# Teknic_motor_io.net
KiCad netlist of a schematic drawn in EAGLE
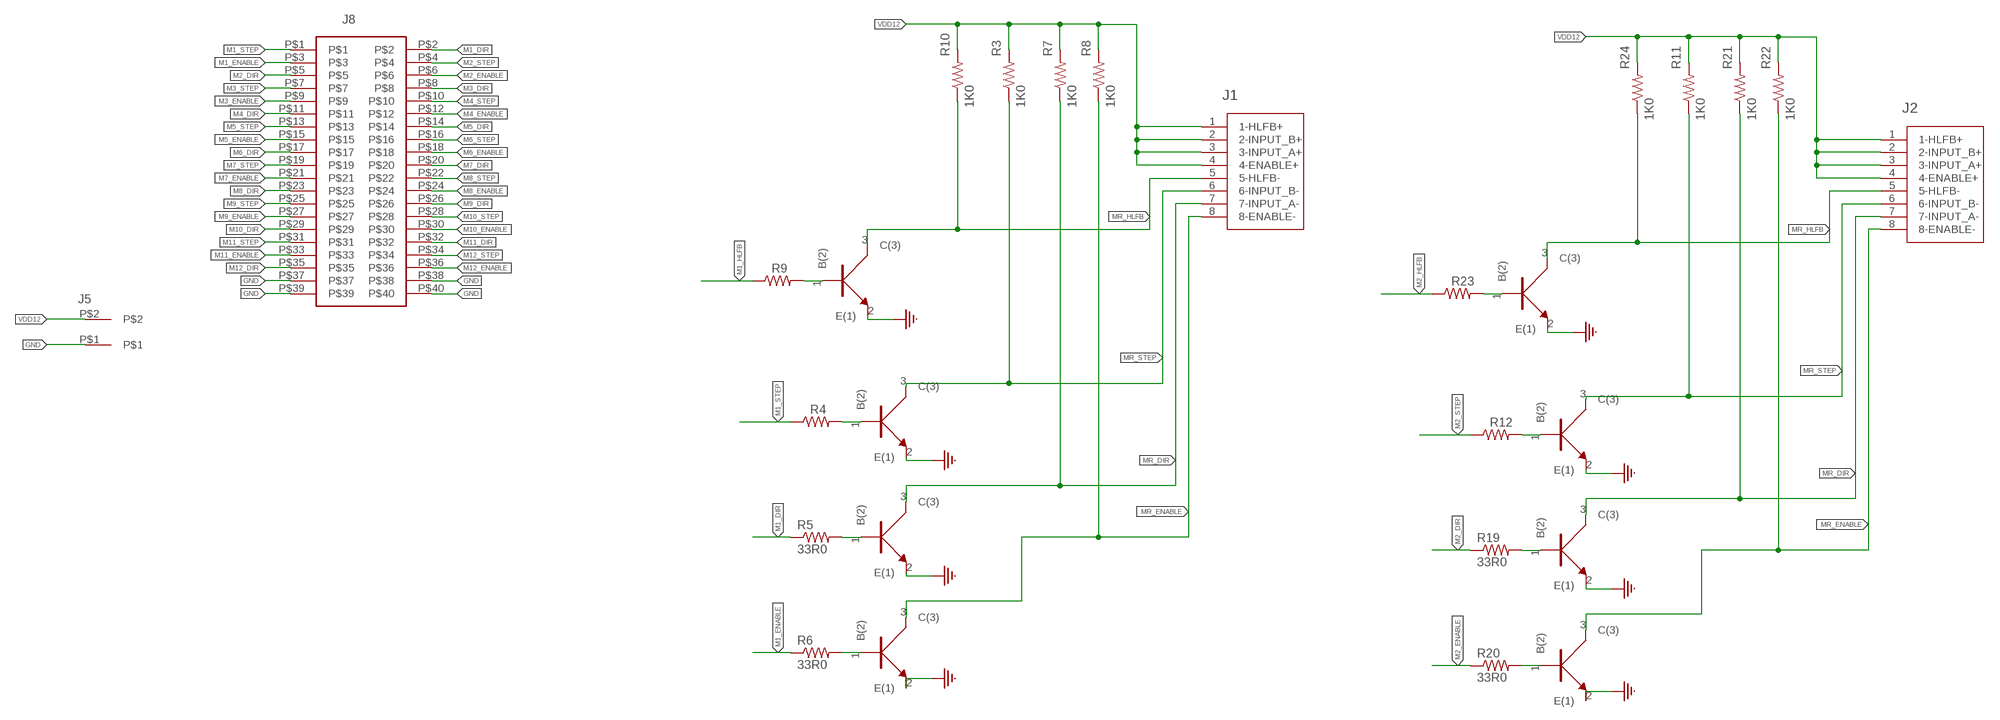
[diagram p0: schematic, sheet 1, part 1 of 3]
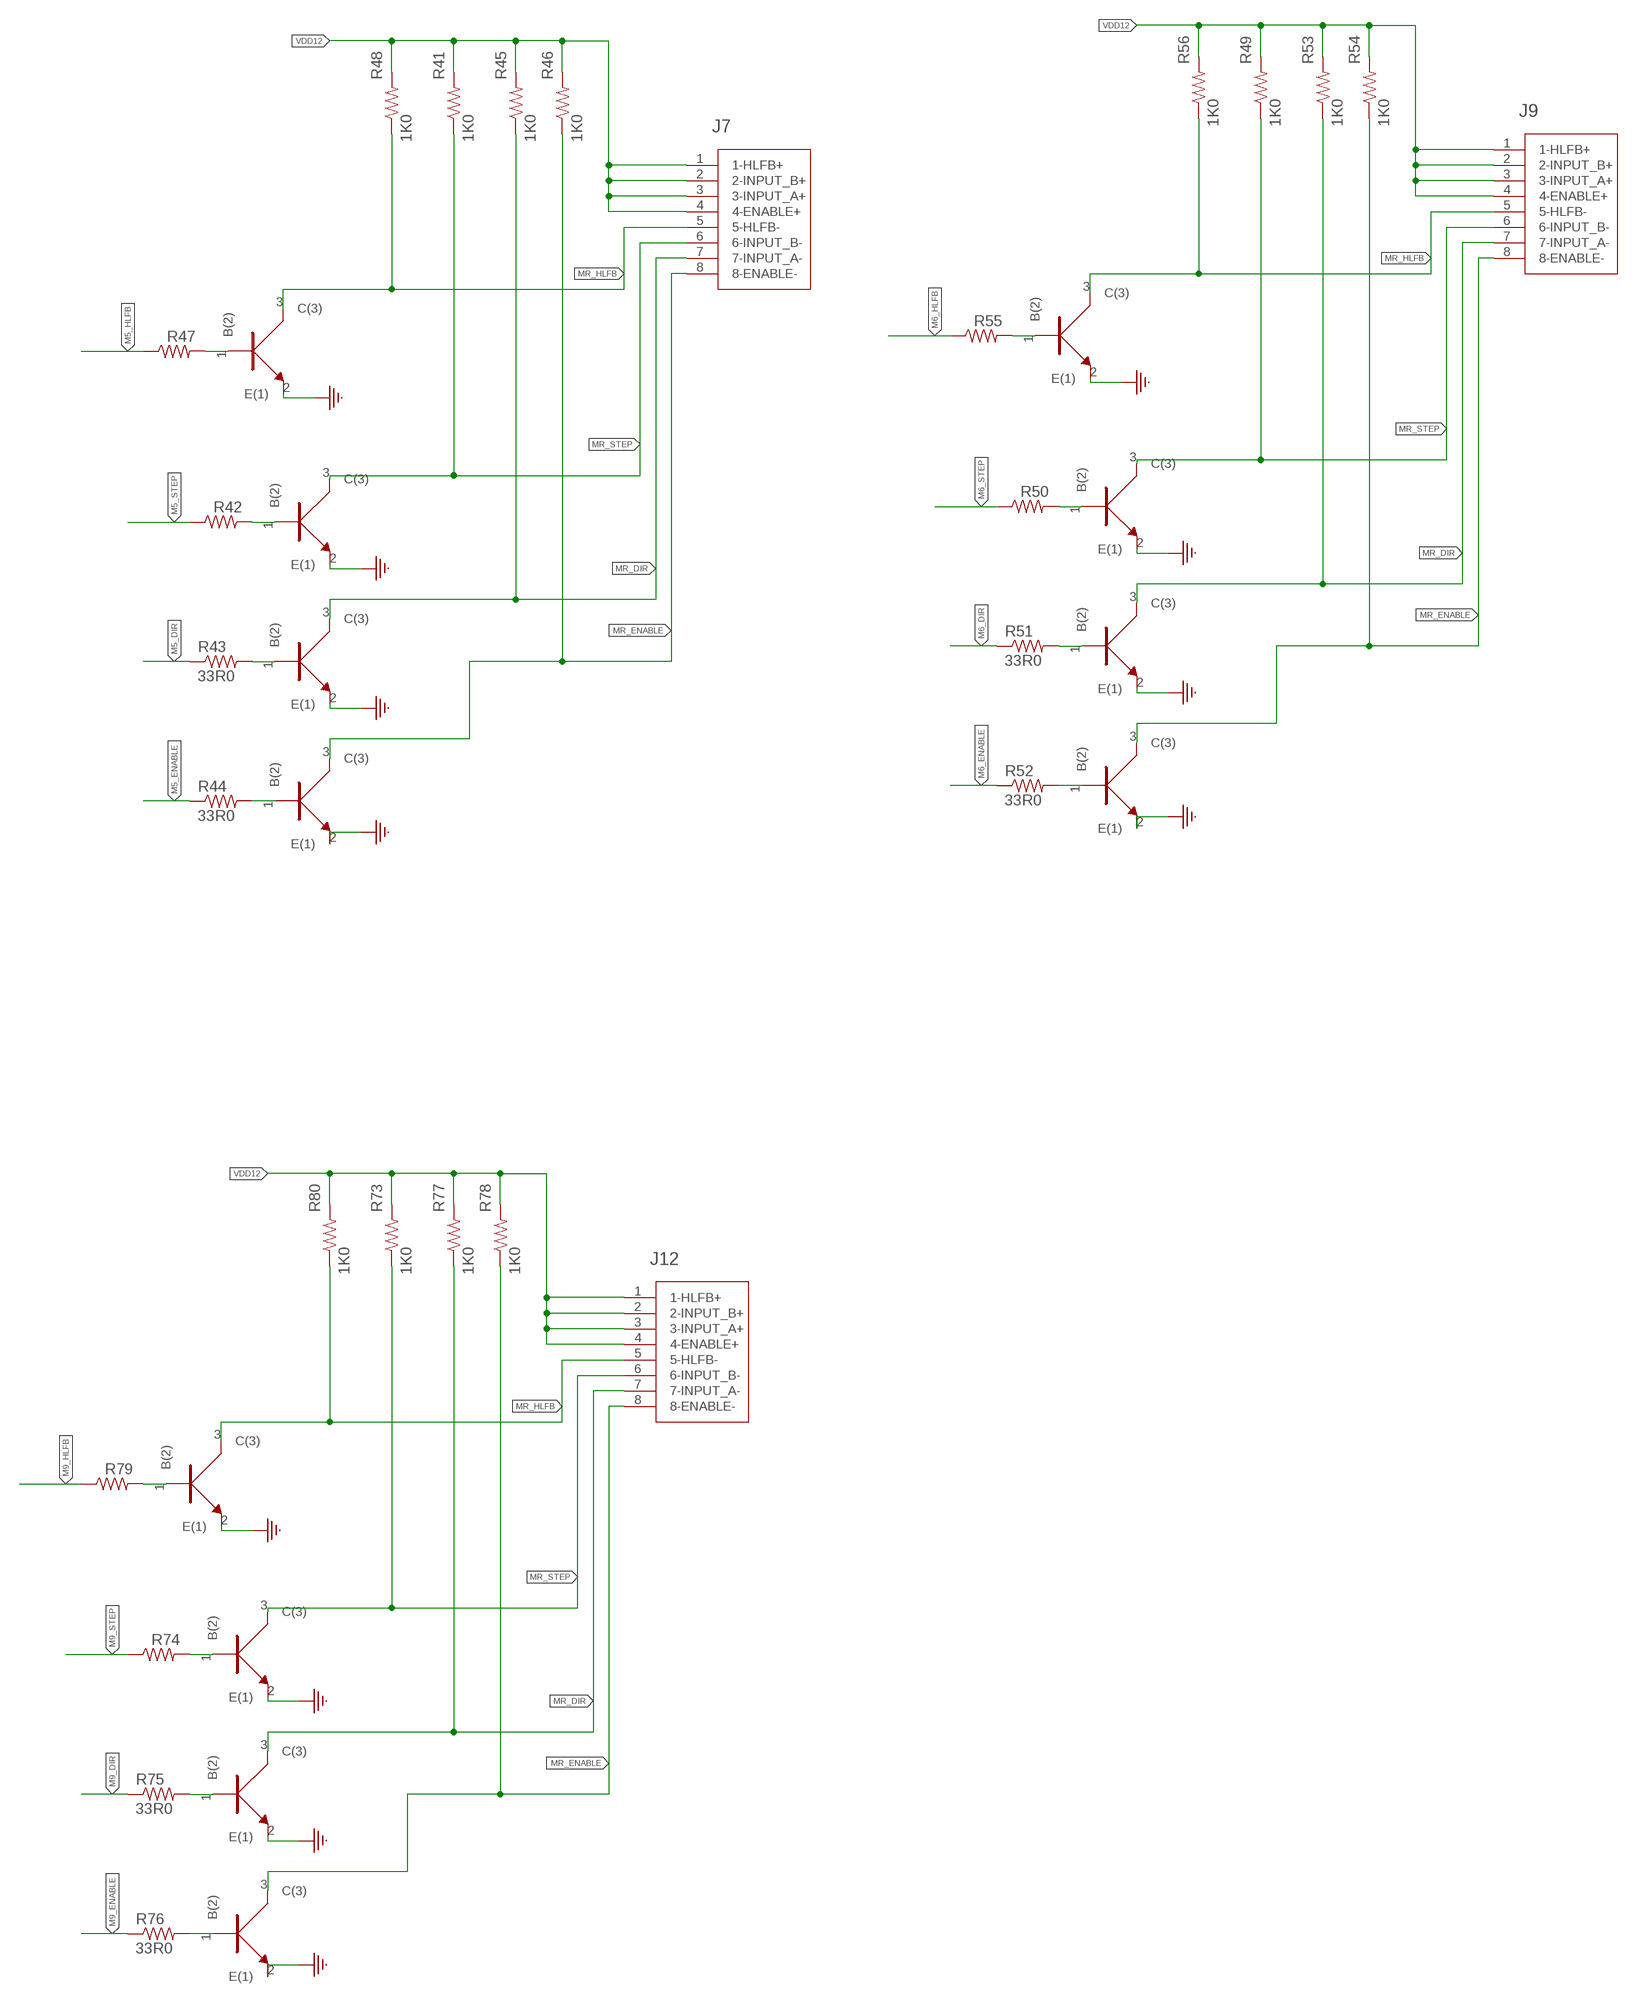
[diagram p1: schematic, sheet 1, part 2 of 3]
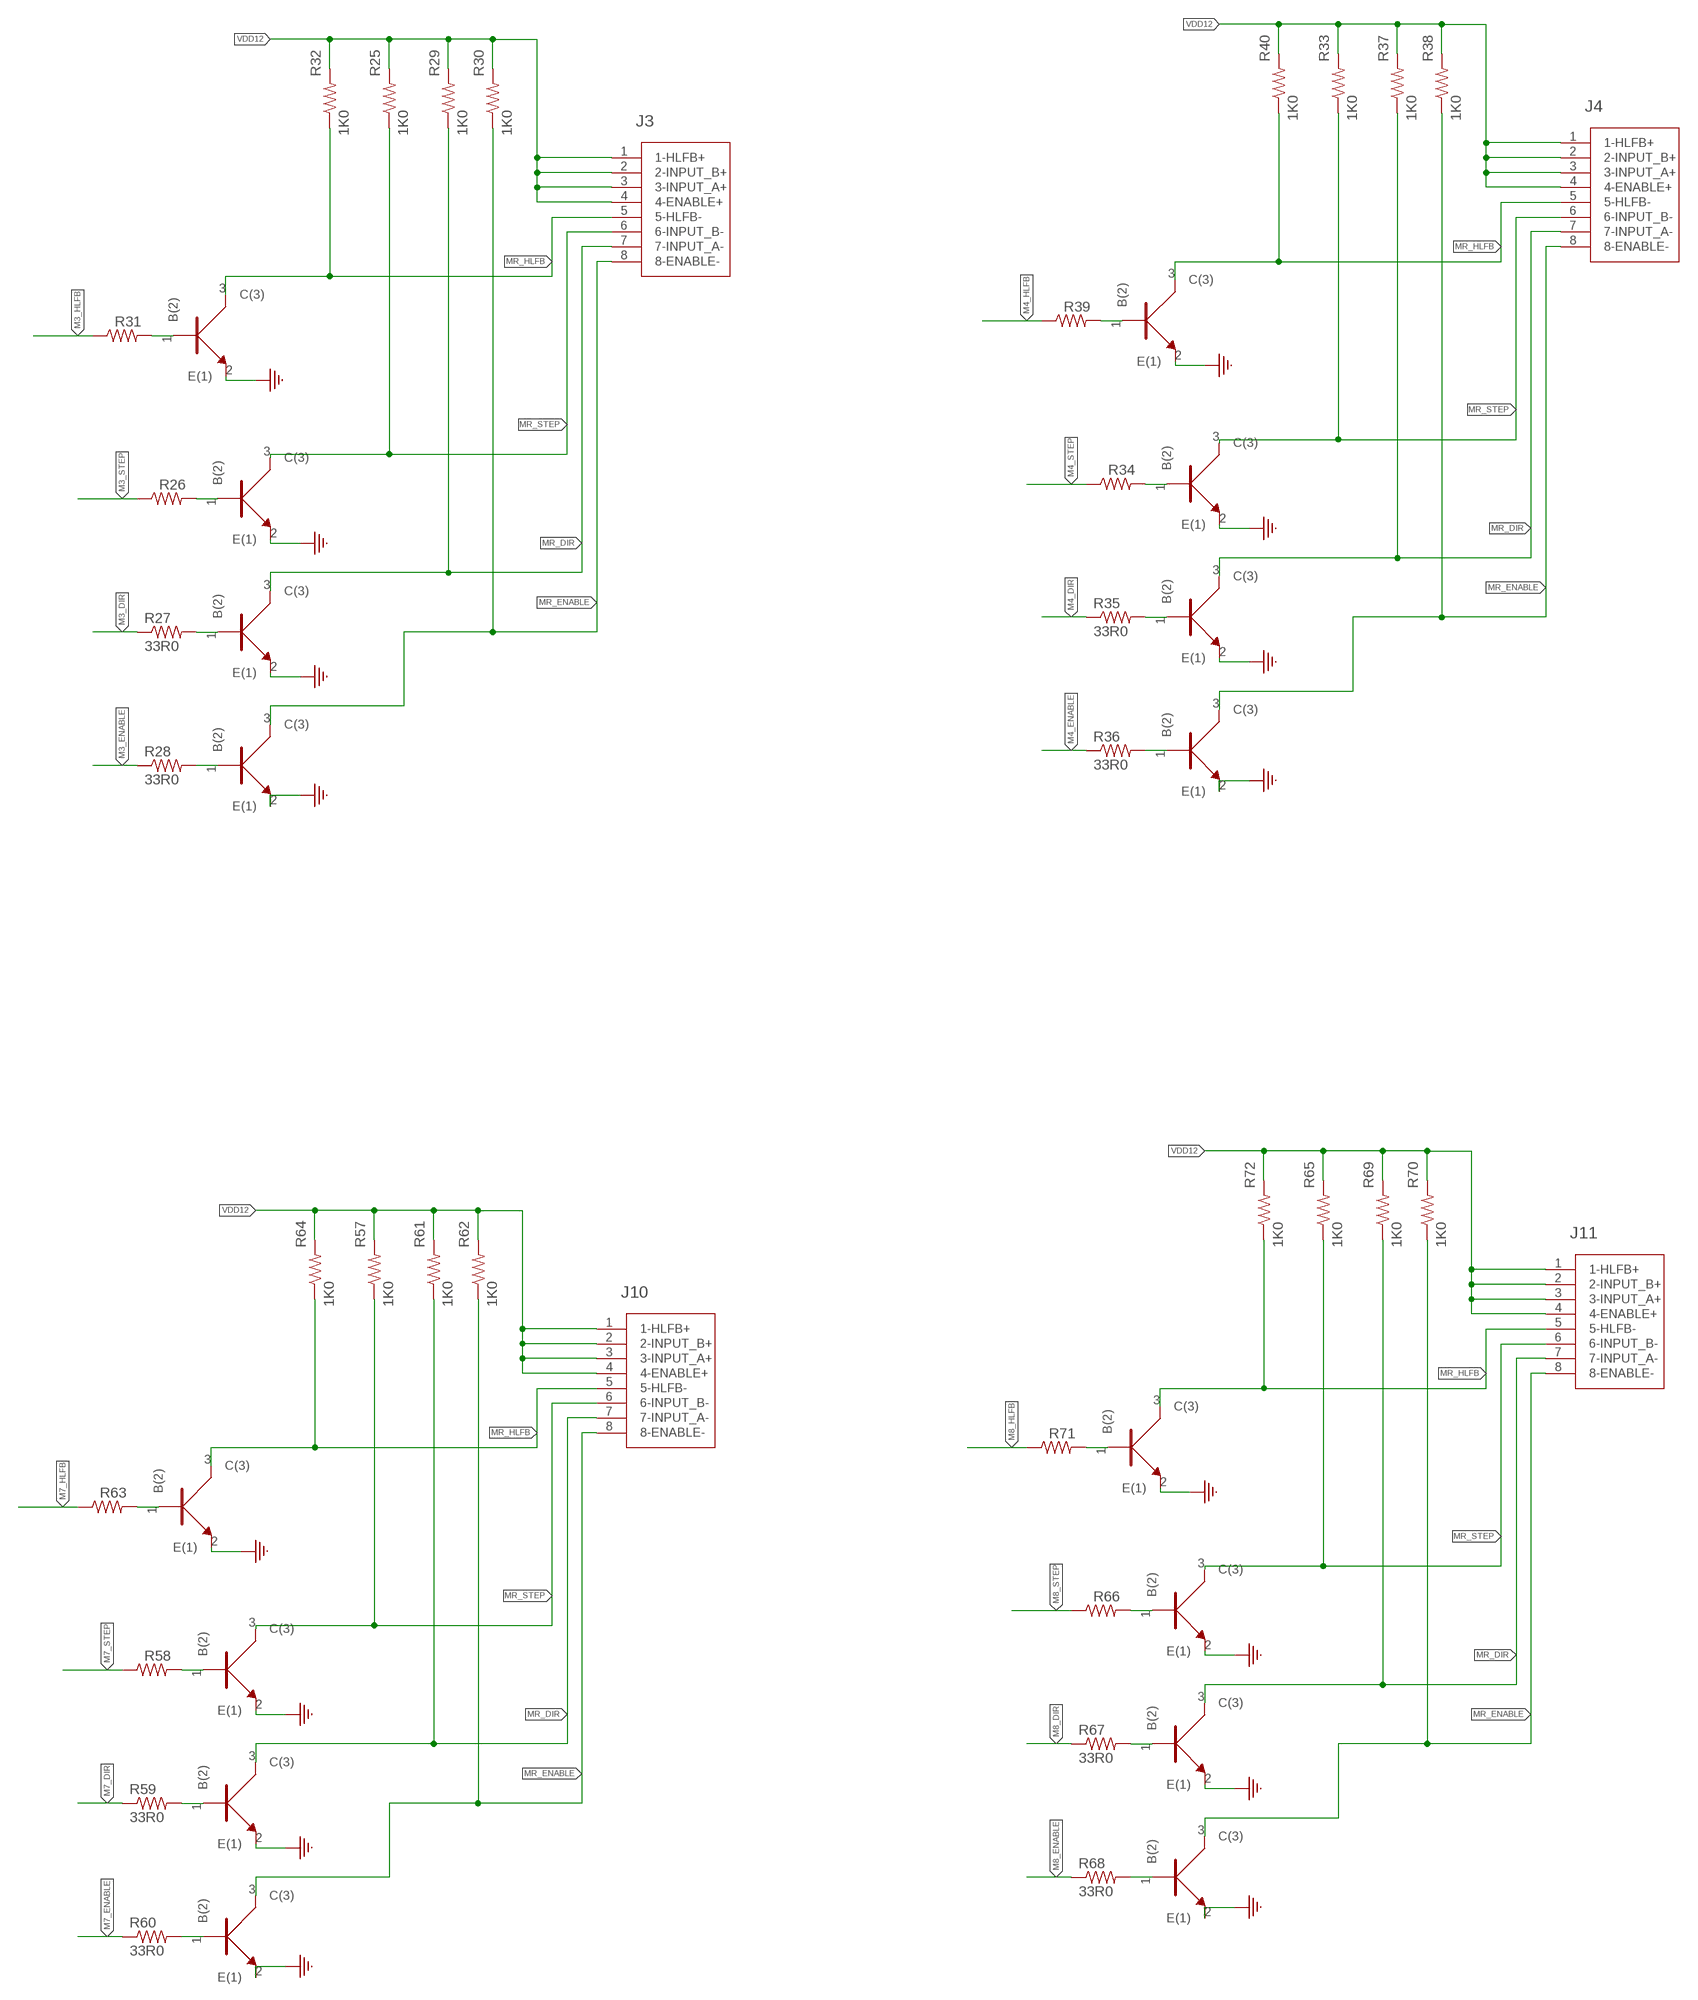
[diagram p2: schematic, sheet 1, part 3 of 3]

(export (version "E")
  (design (tool "Eeschema 10.0.6"))
  (components
    (comp (ref "J1")
      (value "TEKNIC_8PIN_MOTOR")
      (footprint "eagle-import:CON_39281083")
      (fields
        (field (name "MANUFACTURER_PART_NUMBER") "39281083")
        (field (name "COPYRIGHT") "Copyright (C) 2022 Ultra Librarian. All rights reserved.")
      )
      (libsource (lib "eagle-import") (part "TEKNIC_8PIN_MOTOR"))
    )
    (comp (ref "J2")
      (value "TEKNIC_8PIN_MOTOR")
      (footprint "eagle-import:CON_39281083")
      (fields
        (field (name "MANUFACTURER_PART_NUMBER") "39281083")
        (field (name "COPYRIGHT") "Copyright (C) 2022 Ultra Librarian. All rights reserved.")
      )
      (libsource (lib "eagle-import") (part "TEKNIC_8PIN_MOTOR"))
    )
    (comp (ref "J3")
      (value "TEKNIC_8PIN_MOTOR")
      (footprint "eagle-import:CON_39281083")
      (fields
        (field (name "MANUFACTURER_PART_NUMBER") "39281083")
        (field (name "COPYRIGHT") "Copyright (C) 2022 Ultra Librarian. All rights reserved.")
      )
      (libsource (lib "eagle-import") (part "TEKNIC_8PIN_MOTOR"))
    )
    (comp (ref "J4")
      (value "TEKNIC_8PIN_MOTOR")
      (footprint "eagle-import:CON_39281083")
      (fields
        (field (name "MANUFACTURER_PART_NUMBER") "39281083")
        (field (name "COPYRIGHT") "Copyright (C) 2022 Ultra Librarian. All rights reserved.")
      )
      (libsource (lib "eagle-import") (part "TEKNIC_8PIN_MOTOR"))
    )
    (comp (ref "J5")
      (value "2-pos")
      (footprint "eagle-import:2_3.81MM_PITCH")
      (fields (field (name "PARTNO") "691322310002"))
      (libsource (lib "eagle-import") (part "3.81MM_1_X_2_RT_ANGLE_PLUG_HEADER"))
    )
    (comp (ref "J7")
      (value "TEKNIC_8PIN_MOTOR")
      (footprint "eagle-import:CON_39281083")
      (fields
        (field (name "MANUFACTURER_PART_NUMBER") "39281083")
        (field (name "COPYRIGHT") "Copyright (C) 2022 Ultra Librarian. All rights reserved.")
      )
      (libsource (lib "eagle-import") (part "TEKNIC_8PIN_MOTOR"))
    )
    (comp (ref "J8")
      (value "40-pos")
      (footprint "eagle-import:HEADER_2_X_20_.1_INCH")
      (fields (field (name "PARTNO") "61304021021"))
      (libsource (lib "eagle-import") (part "HEADER_2_X_20_GENERIC"))
    )
    (comp (ref "J9")
      (value "TEKNIC_8PIN_MOTOR")
      (footprint "eagle-import:CON_39281083")
      (fields
        (field (name "MANUFACTURER_PART_NUMBER") "39281083")
        (field (name "COPYRIGHT") "Copyright (C) 2022 Ultra Librarian. All rights reserved.")
      )
      (libsource (lib "eagle-import") (part "TEKNIC_8PIN_MOTOR"))
    )
    (comp (ref "J10")
      (value "TEKNIC_8PIN_MOTOR")
      (footprint "eagle-import:CON_39281083")
      (fields
        (field (name "MANUFACTURER_PART_NUMBER") "39281083")
        (field (name "COPYRIGHT") "Copyright (C) 2022 Ultra Librarian. All rights reserved.")
      )
      (libsource (lib "eagle-import") (part "TEKNIC_8PIN_MOTOR"))
    )
    (comp (ref "J11")
      (value "TEKNIC_8PIN_MOTOR")
      (footprint "eagle-import:CON_39281083")
      (fields
        (field (name "MANUFACTURER_PART_NUMBER") "39281083")
        (field (name "COPYRIGHT") "Copyright (C) 2022 Ultra Librarian. All rights reserved.")
      )
      (libsource (lib "eagle-import") (part "TEKNIC_8PIN_MOTOR"))
    )
    (comp (ref "J12")
      (value "TEKNIC_8PIN_MOTOR")
      (footprint "eagle-import:CON_39281083")
      (fields
        (field (name "MANUFACTURER_PART_NUMBER") "39281083")
        (field (name "COPYRIGHT") "Copyright (C) 2022 Ultra Librarian. All rights reserved.")
      )
      (libsource (lib "eagle-import") (part "TEKNIC_8PIN_MOTOR"))
    )
    (comp (ref "R3")
      (value "1K0")
      (footprint "eagle-import:0402")
      (fields (field (name "PARTNO") "CRG0402J1K0"))
      (libsource (lib "eagle-import") (part "R_0402_1K0"))
    )
    (comp (ref "R4")
      (value "33R0")
      (footprint "eagle-import:0402")
      (fields (field (name "PARTNO") "RMCF0402JT33R0"))
      (libsource (lib "eagle-import") (part "R_0402_33R0"))
    )
    (comp (ref "R5")
      (value "33R0")
      (footprint "eagle-import:0402")
      (fields (field (name "PARTNO") "RMCF0402JT33R0"))
      (libsource (lib "eagle-import") (part "R_0402_33R0"))
    )
    (comp (ref "R6")
      (value "33R0")
      (footprint "eagle-import:0402")
      (fields (field (name "PARTNO") "RMCF0402JT33R0"))
      (libsource (lib "eagle-import") (part "R_0402_33R0"))
    )
    (comp (ref "R7")
      (value "1K0")
      (footprint "eagle-import:0402")
      (fields (field (name "PARTNO") "CRG0402J1K0"))
      (libsource (lib "eagle-import") (part "R_0402_1K0"))
    )
    (comp (ref "R8")
      (value "1K0")
      (footprint "eagle-import:0402")
      (fields (field (name "PARTNO") "CRG0402J1K0"))
      (libsource (lib "eagle-import") (part "R_0402_1K0"))
    )
    (comp (ref "R9")
      (value "33R0")
      (footprint "eagle-import:0402")
      (fields (field (name "PARTNO") "RMCF0402JT33R0"))
      (libsource (lib "eagle-import") (part "R_0402_33R0"))
    )
    (comp (ref "R10")
      (value "1K0")
      (footprint "eagle-import:0402")
      (fields (field (name "PARTNO") "CRG0402J1K0"))
      (libsource (lib "eagle-import") (part "R_0402_1K0"))
    )
    (comp (ref "R11")
      (value "1K0")
      (footprint "eagle-import:0402")
      (fields (field (name "PARTNO") "CRG0402J1K0"))
      (libsource (lib "eagle-import") (part "R_0402_1K0"))
    )
    (comp (ref "R12")
      (value "33R0")
      (footprint "eagle-import:0402")
      (fields (field (name "PARTNO") "RMCF0402JT33R0"))
      (libsource (lib "eagle-import") (part "R_0402_33R0"))
    )
    (comp (ref "R19")
      (value "33R0")
      (footprint "eagle-import:0402")
      (fields (field (name "PARTNO") "RMCF0402JT33R0"))
      (libsource (lib "eagle-import") (part "R_0402_33R0"))
    )
    (comp (ref "R20")
      (value "33R0")
      (footprint "eagle-import:0402")
      (fields (field (name "PARTNO") "RMCF0402JT33R0"))
      (libsource (lib "eagle-import") (part "R_0402_33R0"))
    )
    (comp (ref "R21")
      (value "1K0")
      (footprint "eagle-import:0402")
      (fields (field (name "PARTNO") "CRG0402J1K0"))
      (libsource (lib "eagle-import") (part "R_0402_1K0"))
    )
    (comp (ref "R22")
      (value "1K0")
      (footprint "eagle-import:0402")
      (fields (field (name "PARTNO") "CRG0402J1K0"))
      (libsource (lib "eagle-import") (part "R_0402_1K0"))
    )
    (comp (ref "R23")
      (value "33R0")
      (footprint "eagle-import:0402")
      (fields (field (name "PARTNO") "RMCF0402JT33R0"))
      (libsource (lib "eagle-import") (part "R_0402_33R0"))
    )
    (comp (ref "R24")
      (value "1K0")
      (footprint "eagle-import:0402")
      (fields (field (name "PARTNO") "CRG0402J1K0"))
      (libsource (lib "eagle-import") (part "R_0402_1K0"))
    )
    (comp (ref "R25")
      (value "1K0")
      (footprint "eagle-import:0402")
      (fields (field (name "PARTNO") "CRG0402J1K0"))
      (libsource (lib "eagle-import") (part "R_0402_1K0"))
    )
    (comp (ref "R26")
      (value "33R0")
      (footprint "eagle-import:0402")
      (fields (field (name "PARTNO") "RMCF0402JT33R0"))
      (libsource (lib "eagle-import") (part "R_0402_33R0"))
    )
    (comp (ref "R27")
      (value "33R0")
      (footprint "eagle-import:0402")
      (fields (field (name "PARTNO") "RMCF0402JT33R0"))
      (libsource (lib "eagle-import") (part "R_0402_33R0"))
    )
    (comp (ref "R28")
      (value "33R0")
      (footprint "eagle-import:0402")
      (fields (field (name "PARTNO") "RMCF0402JT33R0"))
      (libsource (lib "eagle-import") (part "R_0402_33R0"))
    )
    (comp (ref "R29")
      (value "1K0")
      (footprint "eagle-import:0402")
      (fields (field (name "PARTNO") "CRG0402J1K0"))
      (libsource (lib "eagle-import") (part "R_0402_1K0"))
    )
    (comp (ref "R30")
      (value "1K0")
      (footprint "eagle-import:0402")
      (fields (field (name "PARTNO") "CRG0402J1K0"))
      (libsource (lib "eagle-import") (part "R_0402_1K0"))
    )
    (comp (ref "R31")
      (value "33R0")
      (footprint "eagle-import:0402")
      (fields (field (name "PARTNO") "RMCF0402JT33R0"))
      (libsource (lib "eagle-import") (part "R_0402_33R0"))
    )
    (comp (ref "R32")
      (value "1K0")
      (footprint "eagle-import:0402")
      (fields (field (name "PARTNO") "CRG0402J1K0"))
      (libsource (lib "eagle-import") (part "R_0402_1K0"))
    )
    (comp (ref "R33")
      (value "1K0")
      (footprint "eagle-import:0402")
      (fields (field (name "PARTNO") "CRG0402J1K0"))
      (libsource (lib "eagle-import") (part "R_0402_1K0"))
    )
    (comp (ref "R34")
      (value "33R0")
      (footprint "eagle-import:0402")
      (fields (field (name "PARTNO") "RMCF0402JT33R0"))
      (libsource (lib "eagle-import") (part "R_0402_33R0"))
    )
    (comp (ref "R35")
      (value "33R0")
      (footprint "eagle-import:0402")
      (fields (field (name "PARTNO") "RMCF0402JT33R0"))
      (libsource (lib "eagle-import") (part "R_0402_33R0"))
    )
    (comp (ref "R36")
      (value "33R0")
      (footprint "eagle-import:0402")
      (fields (field (name "PARTNO") "RMCF0402JT33R0"))
      (libsource (lib "eagle-import") (part "R_0402_33R0"))
    )
    (comp (ref "R37")
      (value "1K0")
      (footprint "eagle-import:0402")
      (fields (field (name "PARTNO") "CRG0402J1K0"))
      (libsource (lib "eagle-import") (part "R_0402_1K0"))
    )
    (comp (ref "R38")
      (value "1K0")
      (footprint "eagle-import:0402")
      (fields (field (name "PARTNO") "CRG0402J1K0"))
      (libsource (lib "eagle-import") (part "R_0402_1K0"))
    )
    (comp (ref "R39")
      (value "33R0")
      (footprint "eagle-import:0402")
      (fields (field (name "PARTNO") "RMCF0402JT33R0"))
      (libsource (lib "eagle-import") (part "R_0402_33R0"))
    )
    (comp (ref "R40")
      (value "1K0")
      (footprint "eagle-import:0402")
      (fields (field (name "PARTNO") "CRG0402J1K0"))
      (libsource (lib "eagle-import") (part "R_0402_1K0"))
    )
    (comp (ref "R41")
      (value "1K0")
      (footprint "eagle-import:0402")
      (fields (field (name "PARTNO") "CRG0402J1K0"))
      (libsource (lib "eagle-import") (part "R_0402_1K0"))
    )
    (comp (ref "R42")
      (value "33R0")
      (footprint "eagle-import:0402")
      (fields (field (name "PARTNO") "RMCF0402JT33R0"))
      (libsource (lib "eagle-import") (part "R_0402_33R0"))
    )
    (comp (ref "R43")
      (value "33R0")
      (footprint "eagle-import:0402")
      (fields (field (name "PARTNO") "RMCF0402JT33R0"))
      (libsource (lib "eagle-import") (part "R_0402_33R0"))
    )
    (comp (ref "R44")
      (value "33R0")
      (footprint "eagle-import:0402")
      (fields (field (name "PARTNO") "RMCF0402JT33R0"))
      (libsource (lib "eagle-import") (part "R_0402_33R0"))
    )
    (comp (ref "R45")
      (value "1K0")
      (footprint "eagle-import:0402")
      (fields (field (name "PARTNO") "CRG0402J1K0"))
      (libsource (lib "eagle-import") (part "R_0402_1K0"))
    )
    (comp (ref "R46")
      (value "1K0")
      (footprint "eagle-import:0402")
      (fields (field (name "PARTNO") "CRG0402J1K0"))
      (libsource (lib "eagle-import") (part "R_0402_1K0"))
    )
    (comp (ref "R47")
      (value "33R0")
      (footprint "eagle-import:0402")
      (fields (field (name "PARTNO") "RMCF0402JT33R0"))
      (libsource (lib "eagle-import") (part "R_0402_33R0"))
    )
    (comp (ref "R48")
      (value "1K0")
      (footprint "eagle-import:0402")
      (fields (field (name "PARTNO") "CRG0402J1K0"))
      (libsource (lib "eagle-import") (part "R_0402_1K0"))
    )
    (comp (ref "R49")
      (value "1K0")
      (footprint "eagle-import:0402")
      (fields (field (name "PARTNO") "CRG0402J1K0"))
      (libsource (lib "eagle-import") (part "R_0402_1K0"))
    )
    (comp (ref "R50")
      (value "33R0")
      (footprint "eagle-import:0402")
      (fields (field (name "PARTNO") "RMCF0402JT33R0"))
      (libsource (lib "eagle-import") (part "R_0402_33R0"))
    )
    (comp (ref "R51")
      (value "33R0")
      (footprint "eagle-import:0402")
      (fields (field (name "PARTNO") "RMCF0402JT33R0"))
      (libsource (lib "eagle-import") (part "R_0402_33R0"))
    )
    (comp (ref "R52")
      (value "33R0")
      (footprint "eagle-import:0402")
      (fields (field (name "PARTNO") "RMCF0402JT33R0"))
      (libsource (lib "eagle-import") (part "R_0402_33R0"))
    )
    (comp (ref "R53")
      (value "1K0")
      (footprint "eagle-import:0402")
      (fields (field (name "PARTNO") "CRG0402J1K0"))
      (libsource (lib "eagle-import") (part "R_0402_1K0"))
    )
    (comp (ref "R54")
      (value "1K0")
      (footprint "eagle-import:0402")
      (fields (field (name "PARTNO") "CRG0402J1K0"))
      (libsource (lib "eagle-import") (part "R_0402_1K0"))
    )
    (comp (ref "R55")
      (value "33R0")
      (footprint "eagle-import:0402")
      (fields (field (name "PARTNO") "RMCF0402JT33R0"))
      (libsource (lib "eagle-import") (part "R_0402_33R0"))
    )
    (comp (ref "R56")
      (value "1K0")
      (footprint "eagle-import:0402")
      (fields (field (name "PARTNO") "CRG0402J1K0"))
      (libsource (lib "eagle-import") (part "R_0402_1K0"))
    )
    (comp (ref "R57")
      (value "1K0")
      (footprint "eagle-import:0402")
      (fields (field (name "PARTNO") "CRG0402J1K0"))
      (libsource (lib "eagle-import") (part "R_0402_1K0"))
    )
    (comp (ref "R58")
      (value "33R0")
      (footprint "eagle-import:0402")
      (fields (field (name "PARTNO") "RMCF0402JT33R0"))
      (libsource (lib "eagle-import") (part "R_0402_33R0"))
    )
    (comp (ref "R59")
      (value "33R0")
      (footprint "eagle-import:0402")
      (fields (field (name "PARTNO") "RMCF0402JT33R0"))
      (libsource (lib "eagle-import") (part "R_0402_33R0"))
    )
    (comp (ref "R60")
      (value "33R0")
      (footprint "eagle-import:0402")
      (fields (field (name "PARTNO") "RMCF0402JT33R0"))
      (libsource (lib "eagle-import") (part "R_0402_33R0"))
    )
    (comp (ref "R61")
      (value "1K0")
      (footprint "eagle-import:0402")
      (fields (field (name "PARTNO") "CRG0402J1K0"))
      (libsource (lib "eagle-import") (part "R_0402_1K0"))
    )
    (comp (ref "R62")
      (value "1K0")
      (footprint "eagle-import:0402")
      (fields (field (name "PARTNO") "CRG0402J1K0"))
      (libsource (lib "eagle-import") (part "R_0402_1K0"))
    )
    (comp (ref "R63")
      (value "33R0")
      (footprint "eagle-import:0402")
      (fields (field (name "PARTNO") "RMCF0402JT33R0"))
      (libsource (lib "eagle-import") (part "R_0402_33R0"))
    )
    (comp (ref "R64")
      (value "1K0")
      (footprint "eagle-import:0402")
      (fields (field (name "PARTNO") "CRG0402J1K0"))
      (libsource (lib "eagle-import") (part "R_0402_1K0"))
    )
    (comp (ref "R65")
      (value "1K0")
      (footprint "eagle-import:0402")
      (fields (field (name "PARTNO") "CRG0402J1K0"))
      (libsource (lib "eagle-import") (part "R_0402_1K0"))
    )
    (comp (ref "R66")
      (value "33R0")
      (footprint "eagle-import:0402")
      (fields (field (name "PARTNO") "RMCF0402JT33R0"))
      (libsource (lib "eagle-import") (part "R_0402_33R0"))
    )
    (comp (ref "R67")
      (value "33R0")
      (footprint "eagle-import:0402")
      (fields (field (name "PARTNO") "RMCF0402JT33R0"))
      (libsource (lib "eagle-import") (part "R_0402_33R0"))
    )
    (comp (ref "R68")
      (value "33R0")
      (footprint "eagle-import:0402")
      (fields (field (name "PARTNO") "RMCF0402JT33R0"))
      (libsource (lib "eagle-import") (part "R_0402_33R0"))
    )
    (comp (ref "R69")
      (value "1K0")
      (footprint "eagle-import:0402")
      (fields (field (name "PARTNO") "CRG0402J1K0"))
      (libsource (lib "eagle-import") (part "R_0402_1K0"))
    )
    (comp (ref "R70")
      (value "1K0")
      (footprint "eagle-import:0402")
      (fields (field (name "PARTNO") "CRG0402J1K0"))
      (libsource (lib "eagle-import") (part "R_0402_1K0"))
    )
    (comp (ref "R71")
      (value "33R0")
      (footprint "eagle-import:0402")
      (fields (field (name "PARTNO") "RMCF0402JT33R0"))
      (libsource (lib "eagle-import") (part "R_0402_33R0"))
    )
    (comp (ref "R72")
      (value "1K0")
      (footprint "eagle-import:0402")
      (fields (field (name "PARTNO") "CRG0402J1K0"))
      (libsource (lib "eagle-import") (part "R_0402_1K0"))
    )
    (comp (ref "R73")
      (value "1K0")
      (footprint "eagle-import:0402")
      (fields (field (name "PARTNO") "CRG0402J1K0"))
      (libsource (lib "eagle-import") (part "R_0402_1K0"))
    )
    (comp (ref "R74")
      (value "33R0")
      (footprint "eagle-import:0402")
      (fields (field (name "PARTNO") "RMCF0402JT33R0"))
      (libsource (lib "eagle-import") (part "R_0402_33R0"))
    )
    (comp (ref "R75")
      (value "33R0")
      (footprint "eagle-import:0402")
      (fields (field (name "PARTNO") "RMCF0402JT33R0"))
      (libsource (lib "eagle-import") (part "R_0402_33R0"))
    )
    (comp (ref "R76")
      (value "33R0")
      (footprint "eagle-import:0402")
      (fields (field (name "PARTNO") "RMCF0402JT33R0"))
      (libsource (lib "eagle-import") (part "R_0402_33R0"))
    )
    (comp (ref "R77")
      (value "1K0")
      (footprint "eagle-import:0402")
      (fields (field (name "PARTNO") "CRG0402J1K0"))
      (libsource (lib "eagle-import") (part "R_0402_1K0"))
    )
    (comp (ref "R78")
      (value "1K0")
      (footprint "eagle-import:0402")
      (fields (field (name "PARTNO") "CRG0402J1K0"))
      (libsource (lib "eagle-import") (part "R_0402_1K0"))
    )
    (comp (ref "R79")
      (value "33R0")
      (footprint "eagle-import:0402")
      (fields (field (name "PARTNO") "RMCF0402JT33R0"))
      (libsource (lib "eagle-import") (part "R_0402_33R0"))
    )
    (comp (ref "R80")
      (value "1K0")
      (footprint "eagle-import:0402")
      (fields (field (name "PARTNO") "CRG0402J1K0"))
      (libsource (lib "eagle-import") (part "R_0402_1K0"))
    )
    (comp (ref "U2")
      (value "NPN")
      (footprint "eagle-import:SOT323")
      (fields (field (name "PARTNO") "BC846BW_NPN"))
      (libsource (lib "eagle-import") (part "BC846BW"))
    )
    (comp (ref "U3")
      (value "NPN")
      (footprint "eagle-import:SOT323")
      (fields (field (name "PARTNO") "BC846BW_NPN"))
      (libsource (lib "eagle-import") (part "BC846BW"))
    )
    (comp (ref "U4")
      (value "NPN")
      (footprint "eagle-import:SOT323")
      (fields (field (name "PARTNO") "BC846BW_NPN"))
      (libsource (lib "eagle-import") (part "BC846BW"))
    )
    (comp (ref "U5")
      (value "NPN")
      (footprint "eagle-import:SOT323")
      (fields (field (name "PARTNO") "BC846BW_NPN"))
      (libsource (lib "eagle-import") (part "BC846BW"))
    )
    (comp (ref "U6")
      (value "NPN")
      (footprint "eagle-import:SOT323")
      (fields (field (name "PARTNO") "BC846BW_NPN"))
      (libsource (lib "eagle-import") (part "BC846BW"))
    )
    (comp (ref "U10")
      (value "NPN")
      (footprint "eagle-import:SOT323")
      (fields (field (name "PARTNO") "BC846BW_NPN"))
      (libsource (lib "eagle-import") (part "BC846BW"))
    )
    (comp (ref "U11")
      (value "NPN")
      (footprint "eagle-import:SOT323")
      (fields (field (name "PARTNO") "BC846BW_NPN"))
      (libsource (lib "eagle-import") (part "BC846BW"))
    )
    (comp (ref "U12")
      (value "NPN")
      (footprint "eagle-import:SOT323")
      (fields (field (name "PARTNO") "BC846BW_NPN"))
      (libsource (lib "eagle-import") (part "BC846BW"))
    )
    (comp (ref "U13")
      (value "NPN")
      (footprint "eagle-import:SOT323")
      (fields (field (name "PARTNO") "BC846BW_NPN"))
      (libsource (lib "eagle-import") (part "BC846BW"))
    )
    (comp (ref "U14")
      (value "NPN")
      (footprint "eagle-import:SOT323")
      (fields (field (name "PARTNO") "BC846BW_NPN"))
      (libsource (lib "eagle-import") (part "BC846BW"))
    )
    (comp (ref "U15")
      (value "NPN")
      (footprint "eagle-import:SOT323")
      (fields (field (name "PARTNO") "BC846BW_NPN"))
      (libsource (lib "eagle-import") (part "BC846BW"))
    )
    (comp (ref "U16")
      (value "NPN")
      (footprint "eagle-import:SOT323")
      (fields (field (name "PARTNO") "BC846BW_NPN"))
      (libsource (lib "eagle-import") (part "BC846BW"))
    )
    (comp (ref "U17")
      (value "NPN")
      (footprint "eagle-import:SOT323")
      (fields (field (name "PARTNO") "BC846BW_NPN"))
      (libsource (lib "eagle-import") (part "BC846BW"))
    )
    (comp (ref "U18")
      (value "NPN")
      (footprint "eagle-import:SOT323")
      (fields (field (name "PARTNO") "BC846BW_NPN"))
      (libsource (lib "eagle-import") (part "BC846BW"))
    )
    (comp (ref "U19")
      (value "NPN")
      (footprint "eagle-import:SOT323")
      (fields (field (name "PARTNO") "BC846BW_NPN"))
      (libsource (lib "eagle-import") (part "BC846BW"))
    )
    (comp (ref "U20")
      (value "NPN")
      (footprint "eagle-import:SOT323")
      (fields (field (name "PARTNO") "BC846BW_NPN"))
      (libsource (lib "eagle-import") (part "BC846BW"))
    )
    (comp (ref "U21")
      (value "NPN")
      (footprint "eagle-import:SOT323")
      (fields (field (name "PARTNO") "BC846BW_NPN"))
      (libsource (lib "eagle-import") (part "BC846BW"))
    )
    (comp (ref "U22")
      (value "NPN")
      (footprint "eagle-import:SOT323")
      (fields (field (name "PARTNO") "BC846BW_NPN"))
      (libsource (lib "eagle-import") (part "BC846BW"))
    )
    (comp (ref "U23")
      (value "NPN")
      (footprint "eagle-import:SOT323")
      (fields (field (name "PARTNO") "BC846BW_NPN"))
      (libsource (lib "eagle-import") (part "BC846BW"))
    )
    (comp (ref "U24")
      (value "NPN")
      (footprint "eagle-import:SOT323")
      (fields (field (name "PARTNO") "BC846BW_NPN"))
      (libsource (lib "eagle-import") (part "BC846BW"))
    )
    (comp (ref "U25")
      (value "NPN")
      (footprint "eagle-import:SOT323")
      (fields (field (name "PARTNO") "BC846BW_NPN"))
      (libsource (lib "eagle-import") (part "BC846BW"))
    )
    (comp (ref "U26")
      (value "NPN")
      (footprint "eagle-import:SOT323")
      (fields (field (name "PARTNO") "BC846BW_NPN"))
      (libsource (lib "eagle-import") (part "BC846BW"))
    )
    (comp (ref "U27")
      (value "NPN")
      (footprint "eagle-import:SOT323")
      (fields (field (name "PARTNO") "BC846BW_NPN"))
      (libsource (lib "eagle-import") (part "BC846BW"))
    )
    (comp (ref "U28")
      (value "NPN")
      (footprint "eagle-import:SOT323")
      (fields (field (name "PARTNO") "BC846BW_NPN"))
      (libsource (lib "eagle-import") (part "BC846BW"))
    )
    (comp (ref "U29")
      (value "NPN")
      (footprint "eagle-import:SOT323")
      (fields (field (name "PARTNO") "BC846BW_NPN"))
      (libsource (lib "eagle-import") (part "BC846BW"))
    )
    (comp (ref "U30")
      (value "NPN")
      (footprint "eagle-import:SOT323")
      (fields (field (name "PARTNO") "BC846BW_NPN"))
      (libsource (lib "eagle-import") (part "BC846BW"))
    )
    (comp (ref "U31")
      (value "NPN")
      (footprint "eagle-import:SOT323")
      (fields (field (name "PARTNO") "BC846BW_NPN"))
      (libsource (lib "eagle-import") (part "BC846BW"))
    )
    (comp (ref "U32")
      (value "NPN")
      (footprint "eagle-import:SOT323")
      (fields (field (name "PARTNO") "BC846BW_NPN"))
      (libsource (lib "eagle-import") (part "BC846BW"))
    )
    (comp (ref "U33")
      (value "NPN")
      (footprint "eagle-import:SOT323")
      (fields (field (name "PARTNO") "BC846BW_NPN"))
      (libsource (lib "eagle-import") (part "BC846BW"))
    )
    (comp (ref "U34")
      (value "NPN")
      (footprint "eagle-import:SOT323")
      (fields (field (name "PARTNO") "BC846BW_NPN"))
      (libsource (lib "eagle-import") (part "BC846BW"))
    )
    (comp (ref "U35")
      (value "NPN")
      (footprint "eagle-import:SOT323")
      (fields (field (name "PARTNO") "BC846BW_NPN"))
      (libsource (lib "eagle-import") (part "BC846BW"))
    )
    (comp (ref "U36")
      (value "NPN")
      (footprint "eagle-import:SOT323")
      (fields (field (name "PARTNO") "BC846BW_NPN"))
      (libsource (lib "eagle-import") (part "BC846BW"))
    )
    (comp (ref "U37")
      (value "NPN")
      (footprint "eagle-import:SOT323")
      (fields (field (name "PARTNO") "BC846BW_NPN"))
      (libsource (lib "eagle-import") (part "BC846BW"))
    )
    (comp (ref "U38")
      (value "NPN")
      (footprint "eagle-import:SOT323")
      (fields (field (name "PARTNO") "BC846BW_NPN"))
      (libsource (lib "eagle-import") (part "BC846BW"))
    )
    (comp (ref "U39")
      (value "NPN")
      (footprint "eagle-import:SOT323")
      (fields (field (name "PARTNO") "BC846BW_NPN"))
      (libsource (lib "eagle-import") (part "BC846BW"))
    )
    (comp (ref "U40")
      (value "NPN")
      (footprint "eagle-import:SOT323")
      (fields (field (name "PARTNO") "BC846BW_NPN"))
      (libsource (lib "eagle-import") (part "BC846BW"))
    )
  )
  (nets
    (net (code "1") (name "GND") (class "Default")
      (node (ref "J5") (pin "P$1") (pinfunction "P$1_P$1") (pintype "bidirectional"))
      (node (ref "J8") (pin "P$37") (pinfunction "P$37_P$37") (pintype "bidirectional"))
      (node (ref "J8") (pin "P$38") (pinfunction "P$38_P$38") (pintype "bidirectional"))
      (node (ref "J8") (pin "P$39") (pinfunction "P$39_P$39") (pintype "bidirectional"))
      (node (ref "J8") (pin "P$40") (pinfunction "P$40_P$40") (pintype "bidirectional"))
      (node (ref "U10") (pin "2") (pinfunction "E(1)_2") (pintype "output"))
      (node (ref "U11") (pin "2") (pinfunction "E(1)_2") (pintype "output"))
      (node (ref "U12") (pin "2") (pinfunction "E(1)_2") (pintype "output"))
      (node (ref "U13") (pin "2") (pinfunction "E(1)_2") (pintype "output"))
      (node (ref "U14") (pin "2") (pinfunction "E(1)_2") (pintype "output"))
      (node (ref "U15") (pin "2") (pinfunction "E(1)_2") (pintype "output"))
      (node (ref "U16") (pin "2") (pinfunction "E(1)_2") (pintype "output"))
      (node (ref "U17") (pin "2") (pinfunction "E(1)_2") (pintype "output"))
      (node (ref "U18") (pin "2") (pinfunction "E(1)_2") (pintype "output"))
      (node (ref "U19") (pin "2") (pinfunction "E(1)_2") (pintype "output"))
      (node (ref "U2") (pin "2") (pinfunction "E(1)_2") (pintype "output"))
      (node (ref "U20") (pin "2") (pinfunction "E(1)_2") (pintype "output"))
      (node (ref "U21") (pin "2") (pinfunction "E(1)_2") (pintype "output"))
      (node (ref "U22") (pin "2") (pinfunction "E(1)_2") (pintype "output"))
      (node (ref "U23") (pin "2") (pinfunction "E(1)_2") (pintype "output"))
      (node (ref "U24") (pin "2") (pinfunction "E(1)_2") (pintype "output"))
      (node (ref "U25") (pin "2") (pinfunction "E(1)_2") (pintype "output"))
      (node (ref "U26") (pin "2") (pinfunction "E(1)_2") (pintype "output"))
      (node (ref "U27") (pin "2") (pinfunction "E(1)_2") (pintype "output"))
      (node (ref "U28") (pin "2") (pinfunction "E(1)_2") (pintype "output"))
      (node (ref "U29") (pin "2") (pinfunction "E(1)_2") (pintype "output"))
      (node (ref "U3") (pin "2") (pinfunction "E(1)_2") (pintype "output"))
      (node (ref "U30") (pin "2") (pinfunction "E(1)_2") (pintype "output"))
      (node (ref "U31") (pin "2") (pinfunction "E(1)_2") (pintype "output"))
      (node (ref "U32") (pin "2") (pinfunction "E(1)_2") (pintype "output"))
      (node (ref "U33") (pin "2") (pinfunction "E(1)_2") (pintype "output"))
      (node (ref "U34") (pin "2") (pinfunction "E(1)_2") (pintype "output"))
      (node (ref "U35") (pin "2") (pinfunction "E(1)_2") (pintype "output"))
      (node (ref "U36") (pin "2") (pinfunction "E(1)_2") (pintype "output"))
      (node (ref "U37") (pin "2") (pinfunction "E(1)_2") (pintype "output"))
      (node (ref "U38") (pin "2") (pinfunction "E(1)_2") (pintype "output"))
      (node (ref "U39") (pin "2") (pinfunction "E(1)_2") (pintype "output"))
      (node (ref "U4") (pin "2") (pinfunction "E(1)_2") (pintype "output"))
      (node (ref "U40") (pin "2") (pinfunction "E(1)_2") (pintype "output"))
      (node (ref "U5") (pin "2") (pinfunction "E(1)_2") (pintype "output"))
      (node (ref "U6") (pin "2") (pinfunction "E(1)_2") (pintype "output"))
    )
    (net (code "2") (name "M1_DIR") (class "Default")
      (node (ref "J8") (pin "P$2") (pinfunction "P$2_P$2") (pintype "bidirectional"))
      (node (ref "R5") (pin "P$1") (pinfunction "1_P$1") (pintype "passive"))
    )
    (net (code "3") (name "M1_ENABLE") (class "Default")
      (node (ref "J8") (pin "P$3") (pinfunction "P$3_P$3") (pintype "bidirectional"))
      (node (ref "R6") (pin "P$1") (pinfunction "1_P$1") (pintype "passive"))
    )
    (net (code "4") (name "M1_HLFB") (class "Default")
      (node (ref "R9") (pin "P$1") (pinfunction "1_P$1") (pintype "passive"))
    )
    (net (code "5") (name "M1_STEP") (class "Default")
      (node (ref "J8") (pin "P$1") (pinfunction "P$1_P$1") (pintype "bidirectional"))
      (node (ref "R4") (pin "P$1") (pinfunction "1_P$1") (pintype "passive"))
    )
    (net (code "6") (name "M2_DIR") (class "Default")
      (node (ref "J8") (pin "P$5") (pinfunction "P$5_P$5") (pintype "bidirectional"))
      (node (ref "R19") (pin "P$1") (pinfunction "1_P$1") (pintype "passive"))
    )
    (net (code "7") (name "M2_ENABLE") (class "Default")
      (node (ref "J8") (pin "P$6") (pinfunction "P$6_P$6") (pintype "bidirectional"))
      (node (ref "R20") (pin "P$1") (pinfunction "1_P$1") (pintype "passive"))
    )
    (net (code "8") (name "M2_HLFB") (class "Default")
      (node (ref "R23") (pin "P$1") (pinfunction "1_P$1") (pintype "passive"))
    )
    (net (code "9") (name "M2_STEP") (class "Default")
      (node (ref "J8") (pin "P$4") (pinfunction "P$4_P$4") (pintype "bidirectional"))
      (node (ref "R12") (pin "P$1") (pinfunction "1_P$1") (pintype "passive"))
    )
    (net (code "10") (name "M3_DIR") (class "Default")
      (node (ref "J8") (pin "P$8") (pinfunction "P$8_P$8") (pintype "bidirectional"))
      (node (ref "R27") (pin "P$1") (pinfunction "1_P$1") (pintype "passive"))
    )
    (net (code "11") (name "M3_ENABLE") (class "Default")
      (node (ref "J8") (pin "P$9") (pinfunction "P$9_P$9") (pintype "bidirectional"))
      (node (ref "R28") (pin "P$1") (pinfunction "1_P$1") (pintype "passive"))
    )
    (net (code "12") (name "M3_HLFB") (class "Default")
      (node (ref "R31") (pin "P$1") (pinfunction "1_P$1") (pintype "passive"))
    )
    (net (code "13") (name "M3_STEP") (class "Default")
      (node (ref "J8") (pin "P$7") (pinfunction "P$7_P$7") (pintype "bidirectional"))
      (node (ref "R26") (pin "P$1") (pinfunction "1_P$1") (pintype "passive"))
    )
    (net (code "14") (name "M4_DIR") (class "Default")
      (node (ref "J8") (pin "P$11") (pinfunction "P$11_P$11") (pintype "bidirectional"))
      (node (ref "R35") (pin "P$1") (pinfunction "1_P$1") (pintype "passive"))
    )
    (net (code "15") (name "M4_ENABLE") (class "Default")
      (node (ref "J8") (pin "P$12") (pinfunction "P$12_P$12") (pintype "bidirectional"))
      (node (ref "R36") (pin "P$1") (pinfunction "1_P$1") (pintype "passive"))
    )
    (net (code "16") (name "M4_HLFB") (class "Default")
      (node (ref "R39") (pin "P$1") (pinfunction "1_P$1") (pintype "passive"))
    )
    (net (code "17") (name "M4_STEP") (class "Default")
      (node (ref "J8") (pin "P$10") (pinfunction "P$10_P$10") (pintype "bidirectional"))
      (node (ref "R34") (pin "P$1") (pinfunction "1_P$1") (pintype "passive"))
    )
    (net (code "18") (name "M5_DIR") (class "Default")
      (node (ref "J8") (pin "P$14") (pinfunction "P$14_P$14") (pintype "bidirectional"))
      (node (ref "R43") (pin "P$1") (pinfunction "1_P$1") (pintype "passive"))
    )
    (net (code "19") (name "M5_ENABLE") (class "Default")
      (node (ref "J8") (pin "P$15") (pinfunction "P$15_P$15") (pintype "bidirectional"))
      (node (ref "R44") (pin "P$1") (pinfunction "1_P$1") (pintype "passive"))
    )
    (net (code "20") (name "M5_HLFB") (class "Default")
      (node (ref "R47") (pin "P$1") (pinfunction "1_P$1") (pintype "passive"))
    )
    (net (code "21") (name "M5_STEP") (class "Default")
      (node (ref "J8") (pin "P$13") (pinfunction "P$13_P$13") (pintype "bidirectional"))
      (node (ref "R42") (pin "P$1") (pinfunction "1_P$1") (pintype "passive"))
    )
    (net (code "22") (name "M6_DIR") (class "Default")
      (node (ref "J8") (pin "P$17") (pinfunction "P$17_P$17") (pintype "bidirectional"))
      (node (ref "R51") (pin "P$1") (pinfunction "1_P$1") (pintype "passive"))
    )
    (net (code "23") (name "M6_ENABLE") (class "Default")
      (node (ref "J8") (pin "P$18") (pinfunction "P$18_P$18") (pintype "bidirectional"))
      (node (ref "R52") (pin "P$1") (pinfunction "1_P$1") (pintype "passive"))
    )
    (net (code "24") (name "M6_HLFB") (class "Default")
      (node (ref "R55") (pin "P$1") (pinfunction "1_P$1") (pintype "passive"))
    )
    (net (code "25") (name "M6_STEP") (class "Default")
      (node (ref "J8") (pin "P$16") (pinfunction "P$16_P$16") (pintype "bidirectional"))
      (node (ref "R50") (pin "P$1") (pinfunction "1_P$1") (pintype "passive"))
    )
    (net (code "26") (name "M7_DIR") (class "Default")
      (node (ref "J8") (pin "P$20") (pinfunction "P$20_P$20") (pintype "bidirectional"))
      (node (ref "R59") (pin "P$1") (pinfunction "1_P$1") (pintype "passive"))
    )
    (net (code "27") (name "M7_ENABLE") (class "Default")
      (node (ref "J8") (pin "P$21") (pinfunction "P$21_P$21") (pintype "bidirectional"))
      (node (ref "R60") (pin "P$1") (pinfunction "1_P$1") (pintype "passive"))
    )
    (net (code "28") (name "M7_HLFB") (class "Default")
      (node (ref "R63") (pin "P$1") (pinfunction "1_P$1") (pintype "passive"))
    )
    (net (code "29") (name "M7_STEP") (class "Default")
      (node (ref "J8") (pin "P$19") (pinfunction "P$19_P$19") (pintype "bidirectional"))
      (node (ref "R58") (pin "P$1") (pinfunction "1_P$1") (pintype "passive"))
    )
    (net (code "30") (name "M8_DIR") (class "Default")
      (node (ref "J8") (pin "P$23") (pinfunction "P$23_P$23") (pintype "bidirectional"))
      (node (ref "R67") (pin "P$1") (pinfunction "1_P$1") (pintype "passive"))
    )
    (net (code "31") (name "M8_ENABLE") (class "Default")
      (node (ref "J8") (pin "P$24") (pinfunction "P$24_P$24") (pintype "bidirectional"))
      (node (ref "R68") (pin "P$1") (pinfunction "1_P$1") (pintype "passive"))
    )
    (net (code "32") (name "M8_HLFB") (class "Default")
      (node (ref "R71") (pin "P$1") (pinfunction "1_P$1") (pintype "passive"))
    )
    (net (code "33") (name "M8_STEP") (class "Default")
      (node (ref "J8") (pin "P$22") (pinfunction "P$22_P$22") (pintype "bidirectional"))
      (node (ref "R66") (pin "P$1") (pinfunction "1_P$1") (pintype "passive"))
    )
    (net (code "34") (name "M9_DIR") (class "Default")
      (node (ref "J8") (pin "P$26") (pinfunction "P$26_P$26") (pintype "bidirectional"))
      (node (ref "R75") (pin "P$1") (pinfunction "1_P$1") (pintype "passive"))
    )
    (net (code "35") (name "M9_ENABLE") (class "Default")
      (node (ref "J8") (pin "P$27") (pinfunction "P$27_P$27") (pintype "bidirectional"))
      (node (ref "R76") (pin "P$1") (pinfunction "1_P$1") (pintype "passive"))
    )
    (net (code "36") (name "M9_HLFB") (class "Default")
      (node (ref "R79") (pin "P$1") (pinfunction "1_P$1") (pintype "passive"))
    )
    (net (code "37") (name "M9_STEP") (class "Default")
      (node (ref "J8") (pin "P$25") (pinfunction "P$25_P$25") (pintype "bidirectional"))
      (node (ref "R74") (pin "P$1") (pinfunction "1_P$1") (pintype "passive"))
    )
    (net (code "38") (name "M10_DIR") (class "Default")
      (node (ref "J8") (pin "P$29") (pinfunction "P$29_P$29") (pintype "bidirectional"))
    )
    (net (code "39") (name "M10_ENABLE") (class "Default")
      (node (ref "J8") (pin "P$30") (pinfunction "P$30_P$30") (pintype "bidirectional"))
    )
    (net (code "40") (name "M10_STEP") (class "Default")
      (node (ref "J8") (pin "P$28") (pinfunction "P$28_P$28") (pintype "bidirectional"))
    )
    (net (code "41") (name "M11_DIR") (class "Default")
      (node (ref "J8") (pin "P$32") (pinfunction "P$32_P$32") (pintype "bidirectional"))
    )
    (net (code "42") (name "M11_ENABLE") (class "Default")
      (node (ref "J8") (pin "P$33") (pinfunction "P$33_P$33") (pintype "bidirectional"))
    )
    (net (code "43") (name "M11_STEP") (class "Default")
      (node (ref "J8") (pin "P$31") (pinfunction "P$31_P$31") (pintype "bidirectional"))
    )
    (net (code "44") (name "M12_DIR") (class "Default")
      (node (ref "J8") (pin "P$35") (pinfunction "P$35_P$35") (pintype "bidirectional"))
    )
    (net (code "45") (name "M12_ENABLE") (class "Default")
      (node (ref "J8") (pin "P$36") (pinfunction "P$36_P$36") (pintype "bidirectional"))
    )
    (net (code "46") (name "M12_STEP") (class "Default")
      (node (ref "J8") (pin "P$34") (pinfunction "P$34_P$34") (pintype "bidirectional"))
    )
    (net (code "47") (name "MR_DIR") (class "Default")
      (node (ref "J1") (pin "7") (pinfunction "7-INPUT_A-_7") (pintype "passive"))
      (node (ref "J10") (pin "7") (pinfunction "7-INPUT_A-_7") (pintype "passive"))
      (node (ref "J11") (pin "7") (pinfunction "7-INPUT_A-_7") (pintype "passive"))
      (node (ref "J12") (pin "7") (pinfunction "7-INPUT_A-_7") (pintype "passive"))
      (node (ref "J2") (pin "7") (pinfunction "7-INPUT_A-_7") (pintype "passive"))
      (node (ref "J3") (pin "7") (pinfunction "7-INPUT_A-_7") (pintype "passive"))
      (node (ref "J4") (pin "7") (pinfunction "7-INPUT_A-_7") (pintype "passive"))
      (node (ref "J7") (pin "7") (pinfunction "7-INPUT_A-_7") (pintype "passive"))
      (node (ref "J9") (pin "7") (pinfunction "7-INPUT_A-_7") (pintype "passive"))
      (node (ref "R21") (pin "P$1") (pinfunction "1_P$1") (pintype "passive"))
      (node (ref "R29") (pin "P$1") (pinfunction "1_P$1") (pintype "passive"))
      (node (ref "R37") (pin "P$1") (pinfunction "1_P$1") (pintype "passive"))
      (node (ref "R45") (pin "P$1") (pinfunction "1_P$1") (pintype "passive"))
      (node (ref "R53") (pin "P$1") (pinfunction "1_P$1") (pintype "passive"))
      (node (ref "R61") (pin "P$1") (pinfunction "1_P$1") (pintype "passive"))
      (node (ref "R69") (pin "P$1") (pinfunction "1_P$1") (pintype "passive"))
      (node (ref "R7") (pin "P$1") (pinfunction "1_P$1") (pintype "passive"))
      (node (ref "R77") (pin "P$1") (pinfunction "1_P$1") (pintype "passive"))
      (node (ref "U10") (pin "3") (pinfunction "C(3)_3") (pintype "input"))
      (node (ref "U14") (pin "3") (pinfunction "C(3)_3") (pintype "input"))
      (node (ref "U18") (pin "3") (pinfunction "C(3)_3") (pintype "input"))
      (node (ref "U22") (pin "3") (pinfunction "C(3)_3") (pintype "input"))
      (node (ref "U26") (pin "3") (pinfunction "C(3)_3") (pintype "input"))
      (node (ref "U3") (pin "3") (pinfunction "C(3)_3") (pintype "input"))
      (node (ref "U30") (pin "3") (pinfunction "C(3)_3") (pintype "input"))
      (node (ref "U34") (pin "3") (pinfunction "C(3)_3") (pintype "input"))
      (node (ref "U38") (pin "3") (pinfunction "C(3)_3") (pintype "input"))
    )
    (net (code "48") (name "MR_ENABLE") (class "Default")
      (node (ref "J1") (pin "8") (pinfunction "8-ENABLE-_8") (pintype "passive"))
      (node (ref "J10") (pin "8") (pinfunction "8-ENABLE-_8") (pintype "passive"))
      (node (ref "J11") (pin "8") (pinfunction "8-ENABLE-_8") (pintype "passive"))
      (node (ref "J12") (pin "8") (pinfunction "8-ENABLE-_8") (pintype "passive"))
      (node (ref "J2") (pin "8") (pinfunction "8-ENABLE-_8") (pintype "passive"))
      (node (ref "J3") (pin "8") (pinfunction "8-ENABLE-_8") (pintype "passive"))
      (node (ref "J4") (pin "8") (pinfunction "8-ENABLE-_8") (pintype "passive"))
      (node (ref "J7") (pin "8") (pinfunction "8-ENABLE-_8") (pintype "passive"))
      (node (ref "J9") (pin "8") (pinfunction "8-ENABLE-_8") (pintype "passive"))
      (node (ref "R22") (pin "P$1") (pinfunction "1_P$1") (pintype "passive"))
      (node (ref "R30") (pin "P$1") (pinfunction "1_P$1") (pintype "passive"))
      (node (ref "R38") (pin "P$1") (pinfunction "1_P$1") (pintype "passive"))
      (node (ref "R46") (pin "P$1") (pinfunction "1_P$1") (pintype "passive"))
      (node (ref "R54") (pin "P$1") (pinfunction "1_P$1") (pintype "passive"))
      (node (ref "R62") (pin "P$1") (pinfunction "1_P$1") (pintype "passive"))
      (node (ref "R70") (pin "P$1") (pinfunction "1_P$1") (pintype "passive"))
      (node (ref "R78") (pin "P$1") (pinfunction "1_P$1") (pintype "passive"))
      (node (ref "R8") (pin "P$1") (pinfunction "1_P$1") (pintype "passive"))
      (node (ref "U11") (pin "3") (pinfunction "C(3)_3") (pintype "input"))
      (node (ref "U15") (pin "3") (pinfunction "C(3)_3") (pintype "input"))
      (node (ref "U19") (pin "3") (pinfunction "C(3)_3") (pintype "input"))
      (node (ref "U23") (pin "3") (pinfunction "C(3)_3") (pintype "input"))
      (node (ref "U27") (pin "3") (pinfunction "C(3)_3") (pintype "input"))
      (node (ref "U31") (pin "3") (pinfunction "C(3)_3") (pintype "input"))
      (node (ref "U35") (pin "3") (pinfunction "C(3)_3") (pintype "input"))
      (node (ref "U39") (pin "3") (pinfunction "C(3)_3") (pintype "input"))
      (node (ref "U4") (pin "3") (pinfunction "C(3)_3") (pintype "input"))
    )
    (net (code "49") (name "MR_HLFB") (class "Default")
      (node (ref "J1") (pin "5") (pinfunction "5-HLFB-_5") (pintype "passive"))
      (node (ref "J10") (pin "5") (pinfunction "5-HLFB-_5") (pintype "passive"))
      (node (ref "J11") (pin "5") (pinfunction "5-HLFB-_5") (pintype "passive"))
      (node (ref "J12") (pin "5") (pinfunction "5-HLFB-_5") (pintype "passive"))
      (node (ref "J2") (pin "5") (pinfunction "5-HLFB-_5") (pintype "passive"))
      (node (ref "J3") (pin "5") (pinfunction "5-HLFB-_5") (pintype "passive"))
      (node (ref "J4") (pin "5") (pinfunction "5-HLFB-_5") (pintype "passive"))
      (node (ref "J7") (pin "5") (pinfunction "5-HLFB-_5") (pintype "passive"))
      (node (ref "J9") (pin "5") (pinfunction "5-HLFB-_5") (pintype "passive"))
      (node (ref "R10") (pin "P$1") (pinfunction "1_P$1") (pintype "passive"))
      (node (ref "R24") (pin "P$1") (pinfunction "1_P$1") (pintype "passive"))
      (node (ref "R32") (pin "P$1") (pinfunction "1_P$1") (pintype "passive"))
      (node (ref "R40") (pin "P$1") (pinfunction "1_P$1") (pintype "passive"))
      (node (ref "R48") (pin "P$1") (pinfunction "1_P$1") (pintype "passive"))
      (node (ref "R56") (pin "P$1") (pinfunction "1_P$1") (pintype "passive"))
      (node (ref "R64") (pin "P$1") (pinfunction "1_P$1") (pintype "passive"))
      (node (ref "R72") (pin "P$1") (pinfunction "1_P$1") (pintype "passive"))
      (node (ref "R80") (pin "P$1") (pinfunction "1_P$1") (pintype "passive"))
      (node (ref "U12") (pin "3") (pinfunction "C(3)_3") (pintype "input"))
      (node (ref "U16") (pin "3") (pinfunction "C(3)_3") (pintype "input"))
      (node (ref "U20") (pin "3") (pinfunction "C(3)_3") (pintype "input"))
      (node (ref "U24") (pin "3") (pinfunction "C(3)_3") (pintype "input"))
      (node (ref "U28") (pin "3") (pinfunction "C(3)_3") (pintype "input"))
      (node (ref "U32") (pin "3") (pinfunction "C(3)_3") (pintype "input"))
      (node (ref "U36") (pin "3") (pinfunction "C(3)_3") (pintype "input"))
      (node (ref "U40") (pin "3") (pinfunction "C(3)_3") (pintype "input"))
      (node (ref "U5") (pin "3") (pinfunction "C(3)_3") (pintype "input"))
    )
    (net (code "50") (name "MR_STEP") (class "Default")
      (node (ref "J1") (pin "6") (pinfunction "6-INPUT_B-_6") (pintype "passive"))
      (node (ref "J10") (pin "6") (pinfunction "6-INPUT_B-_6") (pintype "passive"))
      (node (ref "J11") (pin "6") (pinfunction "6-INPUT_B-_6") (pintype "passive"))
      (node (ref "J12") (pin "6") (pinfunction "6-INPUT_B-_6") (pintype "passive"))
      (node (ref "J2") (pin "6") (pinfunction "6-INPUT_B-_6") (pintype "passive"))
      (node (ref "J3") (pin "6") (pinfunction "6-INPUT_B-_6") (pintype "passive"))
      (node (ref "J4") (pin "6") (pinfunction "6-INPUT_B-_6") (pintype "passive"))
      (node (ref "J7") (pin "6") (pinfunction "6-INPUT_B-_6") (pintype "passive"))
      (node (ref "J9") (pin "6") (pinfunction "6-INPUT_B-_6") (pintype "passive"))
      (node (ref "R11") (pin "P$1") (pinfunction "1_P$1") (pintype "passive"))
      (node (ref "R25") (pin "P$1") (pinfunction "1_P$1") (pintype "passive"))
      (node (ref "R3") (pin "P$1") (pinfunction "1_P$1") (pintype "passive"))
      (node (ref "R33") (pin "P$1") (pinfunction "1_P$1") (pintype "passive"))
      (node (ref "R41") (pin "P$1") (pinfunction "1_P$1") (pintype "passive"))
      (node (ref "R49") (pin "P$1") (pinfunction "1_P$1") (pintype "passive"))
      (node (ref "R57") (pin "P$1") (pinfunction "1_P$1") (pintype "passive"))
      (node (ref "R65") (pin "P$1") (pinfunction "1_P$1") (pintype "passive"))
      (node (ref "R73") (pin "P$1") (pinfunction "1_P$1") (pintype "passive"))
      (node (ref "U13") (pin "3") (pinfunction "C(3)_3") (pintype "input"))
      (node (ref "U17") (pin "3") (pinfunction "C(3)_3") (pintype "input"))
      (node (ref "U2") (pin "3") (pinfunction "C(3)_3") (pintype "input"))
      (node (ref "U21") (pin "3") (pinfunction "C(3)_3") (pintype "input"))
      (node (ref "U25") (pin "3") (pinfunction "C(3)_3") (pintype "input"))
      (node (ref "U29") (pin "3") (pinfunction "C(3)_3") (pintype "input"))
      (node (ref "U33") (pin "3") (pinfunction "C(3)_3") (pintype "input"))
      (node (ref "U37") (pin "3") (pinfunction "C(3)_3") (pintype "input"))
      (node (ref "U6") (pin "3") (pinfunction "C(3)_3") (pintype "input"))
    )
    (net (code "51") (name "Net-(R4-2)") (class "Default")
      (node (ref "R4") (pin "P$2") (pinfunction "2_P$2") (pintype "passive"))
      (node (ref "U2") (pin "1") (pinfunction "B(2)_1") (pintype "input"))
    )
    (net (code "52") (name "Net-(R5-2)") (class "Default")
      (node (ref "R5") (pin "P$2") (pinfunction "2_P$2") (pintype "passive"))
      (node (ref "U3") (pin "1") (pinfunction "B(2)_1") (pintype "input"))
    )
    (net (code "53") (name "Net-(R6-2)") (class "Default")
      (node (ref "R6") (pin "P$2") (pinfunction "2_P$2") (pintype "passive"))
      (node (ref "U4") (pin "1") (pinfunction "B(2)_1") (pintype "input"))
    )
    (net (code "54") (name "Net-(R9-2)") (class "Default")
      (node (ref "R9") (pin "P$2") (pinfunction "2_P$2") (pintype "passive"))
      (node (ref "U5") (pin "1") (pinfunction "B(2)_1") (pintype "input"))
    )
    (net (code "55") (name "Net-(R12-2)") (class "Default")
      (node (ref "R12") (pin "P$2") (pinfunction "2_P$2") (pintype "passive"))
      (node (ref "U6") (pin "1") (pinfunction "B(2)_1") (pintype "input"))
    )
    (net (code "56") (name "Net-(R19-2)") (class "Default")
      (node (ref "R19") (pin "P$2") (pinfunction "2_P$2") (pintype "passive"))
      (node (ref "U10") (pin "1") (pinfunction "B(2)_1") (pintype "input"))
    )
    (net (code "57") (name "Net-(R20-2)") (class "Default")
      (node (ref "R20") (pin "P$2") (pinfunction "2_P$2") (pintype "passive"))
      (node (ref "U11") (pin "1") (pinfunction "B(2)_1") (pintype "input"))
    )
    (net (code "58") (name "Net-(R23-2)") (class "Default")
      (node (ref "R23") (pin "P$2") (pinfunction "2_P$2") (pintype "passive"))
      (node (ref "U12") (pin "1") (pinfunction "B(2)_1") (pintype "input"))
    )
    (net (code "59") (name "Net-(R26-2)") (class "Default")
      (node (ref "R26") (pin "P$2") (pinfunction "2_P$2") (pintype "passive"))
      (node (ref "U13") (pin "1") (pinfunction "B(2)_1") (pintype "input"))
    )
    (net (code "60") (name "Net-(R27-2)") (class "Default")
      (node (ref "R27") (pin "P$2") (pinfunction "2_P$2") (pintype "passive"))
      (node (ref "U14") (pin "1") (pinfunction "B(2)_1") (pintype "input"))
    )
    (net (code "61") (name "Net-(R28-2)") (class "Default")
      (node (ref "R28") (pin "P$2") (pinfunction "2_P$2") (pintype "passive"))
      (node (ref "U15") (pin "1") (pinfunction "B(2)_1") (pintype "input"))
    )
    (net (code "62") (name "Net-(R31-2)") (class "Default")
      (node (ref "R31") (pin "P$2") (pinfunction "2_P$2") (pintype "passive"))
      (node (ref "U16") (pin "1") (pinfunction "B(2)_1") (pintype "input"))
    )
    (net (code "63") (name "Net-(R34-2)") (class "Default")
      (node (ref "R34") (pin "P$2") (pinfunction "2_P$2") (pintype "passive"))
      (node (ref "U17") (pin "1") (pinfunction "B(2)_1") (pintype "input"))
    )
    (net (code "64") (name "Net-(R35-2)") (class "Default")
      (node (ref "R35") (pin "P$2") (pinfunction "2_P$2") (pintype "passive"))
      (node (ref "U18") (pin "1") (pinfunction "B(2)_1") (pintype "input"))
    )
    (net (code "65") (name "Net-(R36-2)") (class "Default")
      (node (ref "R36") (pin "P$2") (pinfunction "2_P$2") (pintype "passive"))
      (node (ref "U19") (pin "1") (pinfunction "B(2)_1") (pintype "input"))
    )
    (net (code "66") (name "Net-(R39-2)") (class "Default")
      (node (ref "R39") (pin "P$2") (pinfunction "2_P$2") (pintype "passive"))
      (node (ref "U20") (pin "1") (pinfunction "B(2)_1") (pintype "input"))
    )
    (net (code "67") (name "Net-(R42-2)") (class "Default")
      (node (ref "R42") (pin "P$2") (pinfunction "2_P$2") (pintype "passive"))
      (node (ref "U21") (pin "1") (pinfunction "B(2)_1") (pintype "input"))
    )
    (net (code "68") (name "Net-(R43-2)") (class "Default")
      (node (ref "R43") (pin "P$2") (pinfunction "2_P$2") (pintype "passive"))
      (node (ref "U22") (pin "1") (pinfunction "B(2)_1") (pintype "input"))
    )
    (net (code "69") (name "Net-(R44-2)") (class "Default")
      (node (ref "R44") (pin "P$2") (pinfunction "2_P$2") (pintype "passive"))
      (node (ref "U23") (pin "1") (pinfunction "B(2)_1") (pintype "input"))
    )
    (net (code "70") (name "Net-(R47-2)") (class "Default")
      (node (ref "R47") (pin "P$2") (pinfunction "2_P$2") (pintype "passive"))
      (node (ref "U24") (pin "1") (pinfunction "B(2)_1") (pintype "input"))
    )
    (net (code "71") (name "Net-(R50-2)") (class "Default")
      (node (ref "R50") (pin "P$2") (pinfunction "2_P$2") (pintype "passive"))
      (node (ref "U25") (pin "1") (pinfunction "B(2)_1") (pintype "input"))
    )
    (net (code "72") (name "Net-(R51-2)") (class "Default")
      (node (ref "R51") (pin "P$2") (pinfunction "2_P$2") (pintype "passive"))
      (node (ref "U26") (pin "1") (pinfunction "B(2)_1") (pintype "input"))
    )
    (net (code "73") (name "Net-(R52-2)") (class "Default")
      (node (ref "R52") (pin "P$2") (pinfunction "2_P$2") (pintype "passive"))
      (node (ref "U27") (pin "1") (pinfunction "B(2)_1") (pintype "input"))
    )
    (net (code "74") (name "Net-(R55-2)") (class "Default")
      (node (ref "R55") (pin "P$2") (pinfunction "2_P$2") (pintype "passive"))
      (node (ref "U28") (pin "1") (pinfunction "B(2)_1") (pintype "input"))
    )
    (net (code "75") (name "Net-(R58-2)") (class "Default")
      (node (ref "R58") (pin "P$2") (pinfunction "2_P$2") (pintype "passive"))
      (node (ref "U29") (pin "1") (pinfunction "B(2)_1") (pintype "input"))
    )
    (net (code "76") (name "Net-(R59-2)") (class "Default")
      (node (ref "R59") (pin "P$2") (pinfunction "2_P$2") (pintype "passive"))
      (node (ref "U30") (pin "1") (pinfunction "B(2)_1") (pintype "input"))
    )
    (net (code "77") (name "Net-(R60-2)") (class "Default")
      (node (ref "R60") (pin "P$2") (pinfunction "2_P$2") (pintype "passive"))
      (node (ref "U31") (pin "1") (pinfunction "B(2)_1") (pintype "input"))
    )
    (net (code "78") (name "Net-(R63-2)") (class "Default")
      (node (ref "R63") (pin "P$2") (pinfunction "2_P$2") (pintype "passive"))
      (node (ref "U32") (pin "1") (pinfunction "B(2)_1") (pintype "input"))
    )
    (net (code "79") (name "Net-(R66-2)") (class "Default")
      (node (ref "R66") (pin "P$2") (pinfunction "2_P$2") (pintype "passive"))
      (node (ref "U33") (pin "1") (pinfunction "B(2)_1") (pintype "input"))
    )
    (net (code "80") (name "Net-(R67-2)") (class "Default")
      (node (ref "R67") (pin "P$2") (pinfunction "2_P$2") (pintype "passive"))
      (node (ref "U34") (pin "1") (pinfunction "B(2)_1") (pintype "input"))
    )
    (net (code "81") (name "Net-(R68-2)") (class "Default")
      (node (ref "R68") (pin "P$2") (pinfunction "2_P$2") (pintype "passive"))
      (node (ref "U35") (pin "1") (pinfunction "B(2)_1") (pintype "input"))
    )
    (net (code "82") (name "Net-(R71-2)") (class "Default")
      (node (ref "R71") (pin "P$2") (pinfunction "2_P$2") (pintype "passive"))
      (node (ref "U36") (pin "1") (pinfunction "B(2)_1") (pintype "input"))
    )
    (net (code "83") (name "Net-(R74-2)") (class "Default")
      (node (ref "R74") (pin "P$2") (pinfunction "2_P$2") (pintype "passive"))
      (node (ref "U37") (pin "1") (pinfunction "B(2)_1") (pintype "input"))
    )
    (net (code "84") (name "Net-(R75-2)") (class "Default")
      (node (ref "R75") (pin "P$2") (pinfunction "2_P$2") (pintype "passive"))
      (node (ref "U38") (pin "1") (pinfunction "B(2)_1") (pintype "input"))
    )
    (net (code "85") (name "Net-(R76-2)") (class "Default")
      (node (ref "R76") (pin "P$2") (pinfunction "2_P$2") (pintype "passive"))
      (node (ref "U39") (pin "1") (pinfunction "B(2)_1") (pintype "input"))
    )
    (net (code "86") (name "Net-(R79-2)") (class "Default")
      (node (ref "R79") (pin "P$2") (pinfunction "2_P$2") (pintype "passive"))
      (node (ref "U40") (pin "1") (pinfunction "B(2)_1") (pintype "input"))
    )
    (net (code "87") (name "VDD12") (class "Default")
      (node (ref "J1") (pin "1") (pinfunction "1-HLFB+_1") (pintype "passive"))
      (node (ref "J1") (pin "2") (pinfunction "2-INPUT_B+_2") (pintype "passive"))
      (node (ref "J1") (pin "3") (pinfunction "3-INPUT_A+_3") (pintype "passive"))
      (node (ref "J1") (pin "4") (pinfunction "4-ENABLE+_4") (pintype "passive"))
      (node (ref "J10") (pin "1") (pinfunction "1-HLFB+_1") (pintype "passive"))
      (node (ref "J10") (pin "2") (pinfunction "2-INPUT_B+_2") (pintype "passive"))
      (node (ref "J10") (pin "3") (pinfunction "3-INPUT_A+_3") (pintype "passive"))
      (node (ref "J10") (pin "4") (pinfunction "4-ENABLE+_4") (pintype "passive"))
      (node (ref "J11") (pin "1") (pinfunction "1-HLFB+_1") (pintype "passive"))
      (node (ref "J11") (pin "2") (pinfunction "2-INPUT_B+_2") (pintype "passive"))
      (node (ref "J11") (pin "3") (pinfunction "3-INPUT_A+_3") (pintype "passive"))
      (node (ref "J11") (pin "4") (pinfunction "4-ENABLE+_4") (pintype "passive"))
      (node (ref "J12") (pin "1") (pinfunction "1-HLFB+_1") (pintype "passive"))
      (node (ref "J12") (pin "2") (pinfunction "2-INPUT_B+_2") (pintype "passive"))
      (node (ref "J12") (pin "3") (pinfunction "3-INPUT_A+_3") (pintype "passive"))
      (node (ref "J12") (pin "4") (pinfunction "4-ENABLE+_4") (pintype "passive"))
      (node (ref "J2") (pin "1") (pinfunction "1-HLFB+_1") (pintype "passive"))
      (node (ref "J2") (pin "2") (pinfunction "2-INPUT_B+_2") (pintype "passive"))
      (node (ref "J2") (pin "3") (pinfunction "3-INPUT_A+_3") (pintype "passive"))
      (node (ref "J2") (pin "4") (pinfunction "4-ENABLE+_4") (pintype "passive"))
      (node (ref "J3") (pin "1") (pinfunction "1-HLFB+_1") (pintype "passive"))
      (node (ref "J3") (pin "2") (pinfunction "2-INPUT_B+_2") (pintype "passive"))
      (node (ref "J3") (pin "3") (pinfunction "3-INPUT_A+_3") (pintype "passive"))
      (node (ref "J3") (pin "4") (pinfunction "4-ENABLE+_4") (pintype "passive"))
      (node (ref "J4") (pin "1") (pinfunction "1-HLFB+_1") (pintype "passive"))
      (node (ref "J4") (pin "2") (pinfunction "2-INPUT_B+_2") (pintype "passive"))
      (node (ref "J4") (pin "3") (pinfunction "3-INPUT_A+_3") (pintype "passive"))
      (node (ref "J4") (pin "4") (pinfunction "4-ENABLE+_4") (pintype "passive"))
      (node (ref "J5") (pin "P$2") (pinfunction "P$2_P$2") (pintype "bidirectional"))
      (node (ref "J7") (pin "1") (pinfunction "1-HLFB+_1") (pintype "passive"))
      (node (ref "J7") (pin "2") (pinfunction "2-INPUT_B+_2") (pintype "passive"))
      (node (ref "J7") (pin "3") (pinfunction "3-INPUT_A+_3") (pintype "passive"))
      (node (ref "J7") (pin "4") (pinfunction "4-ENABLE+_4") (pintype "passive"))
      (node (ref "J9") (pin "1") (pinfunction "1-HLFB+_1") (pintype "passive"))
      (node (ref "J9") (pin "2") (pinfunction "2-INPUT_B+_2") (pintype "passive"))
      (node (ref "J9") (pin "3") (pinfunction "3-INPUT_A+_3") (pintype "passive"))
      (node (ref "J9") (pin "4") (pinfunction "4-ENABLE+_4") (pintype "passive"))
      (node (ref "R10") (pin "P$2") (pinfunction "2_P$2") (pintype "passive"))
      (node (ref "R11") (pin "P$2") (pinfunction "2_P$2") (pintype "passive"))
      (node (ref "R21") (pin "P$2") (pinfunction "2_P$2") (pintype "passive"))
      (node (ref "R22") (pin "P$2") (pinfunction "2_P$2") (pintype "passive"))
      (node (ref "R24") (pin "P$2") (pinfunction "2_P$2") (pintype "passive"))
      (node (ref "R25") (pin "P$2") (pinfunction "2_P$2") (pintype "passive"))
      (node (ref "R29") (pin "P$2") (pinfunction "2_P$2") (pintype "passive"))
      (node (ref "R3") (pin "P$2") (pinfunction "2_P$2") (pintype "passive"))
      (node (ref "R30") (pin "P$2") (pinfunction "2_P$2") (pintype "passive"))
      (node (ref "R32") (pin "P$2") (pinfunction "2_P$2") (pintype "passive"))
      (node (ref "R33") (pin "P$2") (pinfunction "2_P$2") (pintype "passive"))
      (node (ref "R37") (pin "P$2") (pinfunction "2_P$2") (pintype "passive"))
      (node (ref "R38") (pin "P$2") (pinfunction "2_P$2") (pintype "passive"))
      (node (ref "R40") (pin "P$2") (pinfunction "2_P$2") (pintype "passive"))
      (node (ref "R41") (pin "P$2") (pinfunction "2_P$2") (pintype "passive"))
      (node (ref "R45") (pin "P$2") (pinfunction "2_P$2") (pintype "passive"))
      (node (ref "R46") (pin "P$2") (pinfunction "2_P$2") (pintype "passive"))
      (node (ref "R48") (pin "P$2") (pinfunction "2_P$2") (pintype "passive"))
      (node (ref "R49") (pin "P$2") (pinfunction "2_P$2") (pintype "passive"))
      (node (ref "R53") (pin "P$2") (pinfunction "2_P$2") (pintype "passive"))
      (node (ref "R54") (pin "P$2") (pinfunction "2_P$2") (pintype "passive"))
      (node (ref "R56") (pin "P$2") (pinfunction "2_P$2") (pintype "passive"))
      (node (ref "R57") (pin "P$2") (pinfunction "2_P$2") (pintype "passive"))
      (node (ref "R61") (pin "P$2") (pinfunction "2_P$2") (pintype "passive"))
      (node (ref "R62") (pin "P$2") (pinfunction "2_P$2") (pintype "passive"))
      (node (ref "R64") (pin "P$2") (pinfunction "2_P$2") (pintype "passive"))
      (node (ref "R65") (pin "P$2") (pinfunction "2_P$2") (pintype "passive"))
      (node (ref "R69") (pin "P$2") (pinfunction "2_P$2") (pintype "passive"))
      (node (ref "R7") (pin "P$2") (pinfunction "2_P$2") (pintype "passive"))
      (node (ref "R70") (pin "P$2") (pinfunction "2_P$2") (pintype "passive"))
      (node (ref "R72") (pin "P$2") (pinfunction "2_P$2") (pintype "passive"))
      (node (ref "R73") (pin "P$2") (pinfunction "2_P$2") (pintype "passive"))
      (node (ref "R77") (pin "P$2") (pinfunction "2_P$2") (pintype "passive"))
      (node (ref "R78") (pin "P$2") (pinfunction "2_P$2") (pintype "passive"))
      (node (ref "R8") (pin "P$2") (pinfunction "2_P$2") (pintype "passive"))
      (node (ref "R80") (pin "P$2") (pinfunction "2_P$2") (pintype "passive"))
    )
  )
)
